# MirrorsDualAttenuverter.net
KiCad netlist of a schematic drawn in EAGLE
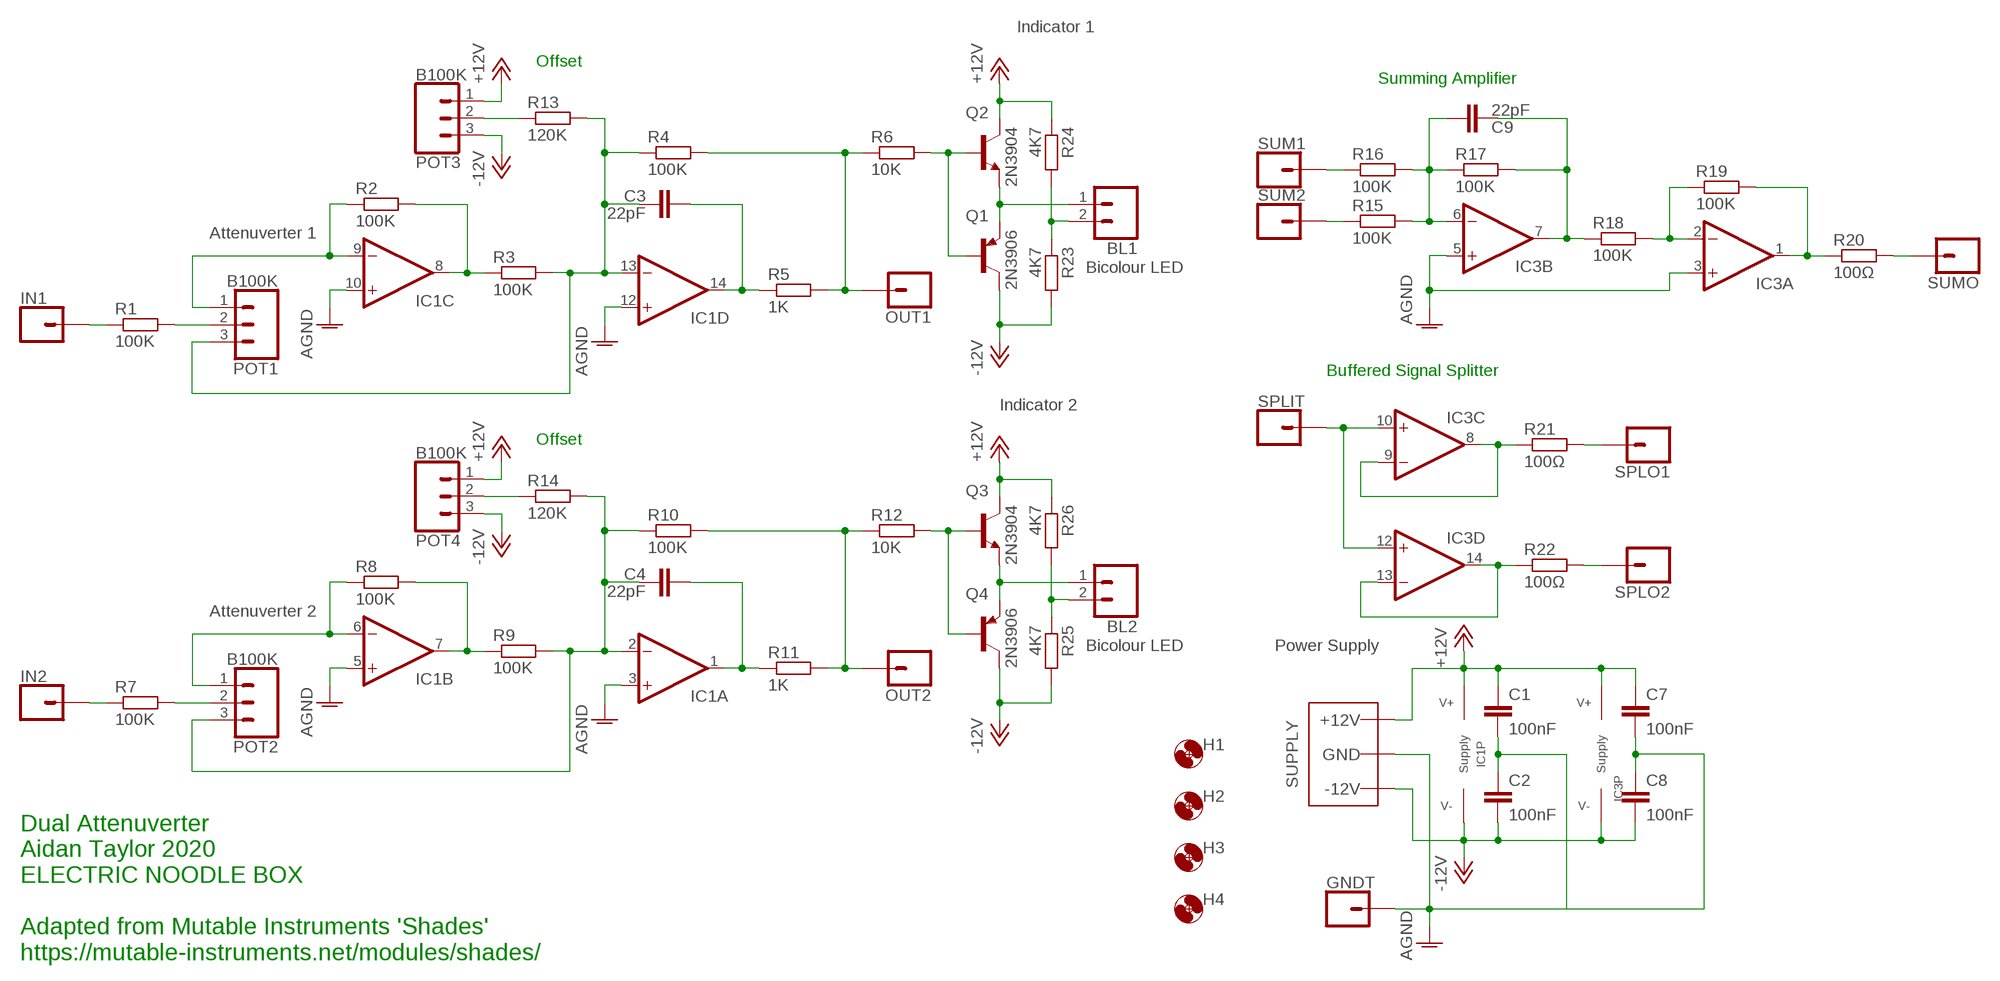
[diagram p0: schematic, sheet 1]

(export (version "E")
  (design (tool "Eeschema 10.0.6"))
  (components
    (comp (ref "BL1")
      (value "2XWIREPAD")
      (footprint "eagle-import:1X02")
      (libsource (lib "eagle-import") (part "2XWIREPAD"))
    )
    (comp (ref "BL2")
      (value "2XWIREPAD")
      (footprint "eagle-import:1X02")
      (libsource (lib "eagle-import") (part "2XWIREPAD"))
    )
    (comp (ref "C1")
      (value "100nF")
      (footprint "eagle-import:C050-025X075")
      (libsource (lib "eagle-import") (part "C-EU050-025X075"))
    )
    (comp (ref "C2")
      (value "100nF")
      (footprint "eagle-import:C050-025X075")
      (libsource (lib "eagle-import") (part "C-EU050-025X075"))
    )
    (comp (ref "C3")
      (value "22pF")
      (footprint "eagle-import:C050-025X075")
      (libsource (lib "eagle-import") (part "C-EU050-025X075"))
    )
    (comp (ref "C4")
      (value "22pF")
      (footprint "eagle-import:C050-025X075")
      (libsource (lib "eagle-import") (part "C-EU050-025X075"))
    )
    (comp (ref "C7")
      (value "100nF")
      (footprint "eagle-import:C050-025X075")
      (libsource (lib "eagle-import") (part "C-EU050-025X075"))
    )
    (comp (ref "C8")
      (value "100nF")
      (footprint "eagle-import:C050-025X075")
      (libsource (lib "eagle-import") (part "C-EU050-025X075"))
    )
    (comp (ref "C9")
      (value "22pF")
      (footprint "eagle-import:C050-025X075")
      (libsource (lib "eagle-import") (part "C-EU050-025X075"))
    )
    (comp (ref "GNDT")
      (value "1XWIREPAD")
      (footprint "eagle-import:1X01")
      (libsource (lib "eagle-import") (part "1XWIREPAD"))
    )
    (comp (ref "H1")
      (value "MOUNT-HOLE3.2")
      (footprint "eagle-import:3,2")
      (libsource (lib "eagle-import") (part "MOUNT-HOLE3.2"))
    )
    (comp (ref "H2")
      (value "MOUNT-HOLE3.2")
      (footprint "eagle-import:3,2")
      (libsource (lib "eagle-import") (part "MOUNT-HOLE3.2"))
    )
    (comp (ref "H3")
      (value "MOUNT-HOLE3.2")
      (footprint "eagle-import:3,2")
      (libsource (lib "eagle-import") (part "MOUNT-HOLE3.2"))
    )
    (comp (ref "H4")
      (value "MOUNT-HOLE3.2")
      (footprint "eagle-import:3,2")
      (libsource (lib "eagle-import") (part "MOUNT-HOLE3.2"))
    )
    (comp (ref "IC1")
      (value "TL0X4DIL")
      (footprint "eagle-import:DIL14")
      (libsource (lib "eagle-import") (part "TL0X4DIL"))
    )
    (comp (ref "IC3")
      (value "TL0X4DIL")
      (footprint "eagle-import:DIL14")
      (libsource (lib "eagle-import") (part "TL0X4DIL"))
    )
    (comp (ref "IN1")
      (value "1XWIREPAD")
      (footprint "eagle-import:1X01")
      (libsource (lib "eagle-import") (part "1XWIREPAD"))
    )
    (comp (ref "IN2")
      (value "1XWIREPAD")
      (footprint "eagle-import:1X01")
      (libsource (lib "eagle-import") (part "1XWIREPAD"))
    )
    (comp (ref "OUT1")
      (value "1XWIREPAD")
      (footprint "eagle-import:1X01")
      (libsource (lib "eagle-import") (part "1XWIREPAD"))
    )
    (comp (ref "OUT2")
      (value "1XWIREPAD")
      (footprint "eagle-import:1X01")
      (libsource (lib "eagle-import") (part "1XWIREPAD"))
    )
    (comp (ref "POT1")
      (value "B100K")
      (footprint "eagle-import:1X03")
      (libsource (lib "eagle-import") (part "3XWIREPAD"))
    )
    (comp (ref "POT2")
      (value "B100K")
      (footprint "eagle-import:1X03")
      (libsource (lib "eagle-import") (part "3XWIREPAD"))
    )
    (comp (ref "POT3")
      (value "B100K")
      (footprint "eagle-import:1X03")
      (libsource (lib "eagle-import") (part "3XWIREPAD"))
    )
    (comp (ref "POT4")
      (value "B100K")
      (footprint "eagle-import:1X03")
      (libsource (lib "eagle-import") (part "3XWIREPAD"))
    )
    (comp (ref "Q1")
      (value "2N3906")
      (footprint "eagle-import:TO92")
      (libsource (lib "eagle-import") (part "2N3906"))
    )
    (comp (ref "Q2")
      (value "2N3904")
      (footprint "eagle-import:TO92")
      (libsource (lib "eagle-import") (part "2N3904"))
    )
    (comp (ref "Q3")
      (value "2N3904")
      (footprint "eagle-import:TO92")
      (libsource (lib "eagle-import") (part "2N3904"))
    )
    (comp (ref "Q4")
      (value "2N3906")
      (footprint "eagle-import:TO92")
      (libsource (lib "eagle-import") (part "2N3906"))
    )
    (comp (ref "R1")
      (value "100K")
      (footprint "eagle-import:0207_10")
      (libsource (lib "eagle-import") (part "R-EU_0207/10"))
    )
    (comp (ref "R2")
      (value "100K")
      (footprint "eagle-import:0207_10")
      (libsource (lib "eagle-import") (part "R-EU_0207/10"))
    )
    (comp (ref "R3")
      (value "100K")
      (footprint "eagle-import:0207_10")
      (libsource (lib "eagle-import") (part "R-EU_0207/10"))
    )
    (comp (ref "R4")
      (value "100K")
      (footprint "eagle-import:0207_10")
      (libsource (lib "eagle-import") (part "R-EU_0207/10"))
    )
    (comp (ref "R5")
      (value "1K")
      (footprint "eagle-import:0207_10")
      (libsource (lib "eagle-import") (part "R-EU_0207/10"))
    )
    (comp (ref "R6")
      (value "10K")
      (footprint "eagle-import:0207_10")
      (libsource (lib "eagle-import") (part "R-EU_0207/10"))
    )
    (comp (ref "R7")
      (value "100K")
      (footprint "eagle-import:0207_10")
      (libsource (lib "eagle-import") (part "R-EU_0207/10"))
    )
    (comp (ref "R8")
      (value "100K")
      (footprint "eagle-import:0207_10")
      (libsource (lib "eagle-import") (part "R-EU_0207/10"))
    )
    (comp (ref "R9")
      (value "100K")
      (footprint "eagle-import:0207_10")
      (libsource (lib "eagle-import") (part "R-EU_0207/10"))
    )
    (comp (ref "R10")
      (value "100K")
      (footprint "eagle-import:0207_10")
      (libsource (lib "eagle-import") (part "R-EU_0207/10"))
    )
    (comp (ref "R11")
      (value "1K")
      (footprint "eagle-import:0207_10")
      (libsource (lib "eagle-import") (part "R-EU_0207/10"))
    )
    (comp (ref "R12")
      (value "10K")
      (footprint "eagle-import:0207_10")
      (libsource (lib "eagle-import") (part "R-EU_0207/10"))
    )
    (comp (ref "R13")
      (value "120K")
      (footprint "eagle-import:0207_10")
      (libsource (lib "eagle-import") (part "R-EU_0207/10"))
    )
    (comp (ref "R14")
      (value "120K")
      (footprint "eagle-import:0207_10")
      (libsource (lib "eagle-import") (part "R-EU_0207/10"))
    )
    (comp (ref "R15")
      (value "100K")
      (footprint "eagle-import:0207_10")
      (libsource (lib "eagle-import") (part "R-EU_0207/10"))
    )
    (comp (ref "R16")
      (value "100K")
      (footprint "eagle-import:0207_10")
      (libsource (lib "eagle-import") (part "R-EU_0207/10"))
    )
    (comp (ref "R17")
      (value "100K")
      (footprint "eagle-import:0207_10")
      (libsource (lib "eagle-import") (part "R-EU_0207/10"))
    )
    (comp (ref "R18")
      (value "100K")
      (footprint "eagle-import:0207_10")
      (libsource (lib "eagle-import") (part "R-EU_0207/10"))
    )
    (comp (ref "R19")
      (value "100K")
      (footprint "eagle-import:0207_10")
      (libsource (lib "eagle-import") (part "R-EU_0207/10"))
    )
    (comp (ref "R20")
      (value "100Ω")
      (footprint "eagle-import:0207_10")
      (libsource (lib "eagle-import") (part "R-EU_0207/10"))
    )
    (comp (ref "R21")
      (value "100Ω")
      (footprint "eagle-import:0207_10")
      (libsource (lib "eagle-import") (part "R-EU_0207/10"))
    )
    (comp (ref "R22")
      (value "100Ω")
      (footprint "eagle-import:0207_10")
      (libsource (lib "eagle-import") (part "R-EU_0207/10"))
    )
    (comp (ref "R23")
      (value "4K7")
      (footprint "eagle-import:0207_10")
      (libsource (lib "eagle-import") (part "R-EU_0207/10"))
    )
    (comp (ref "R24")
      (value "4K7")
      (footprint "eagle-import:0207_10")
      (libsource (lib "eagle-import") (part "R-EU_0207/10"))
    )
    (comp (ref "R25")
      (value "4K7")
      (footprint "eagle-import:0207_10")
      (libsource (lib "eagle-import") (part "R-EU_0207/10"))
    )
    (comp (ref "R26")
      (value "4K7")
      (footprint "eagle-import:0207_10")
      (libsource (lib "eagle-import") (part "R-EU_0207/10"))
    )
    (comp (ref "SPLIT")
      (value "1XWIREPAD")
      (footprint "eagle-import:1X01")
      (libsource (lib "eagle-import") (part "1XWIREPAD"))
    )
    (comp (ref "SPLO1")
      (value "1XWIREPAD")
      (footprint "eagle-import:1X01")
      (libsource (lib "eagle-import") (part "1XWIREPAD"))
    )
    (comp (ref "SPLO2")
      (value "1XWIREPAD")
      (footprint "eagle-import:1X01")
      (libsource (lib "eagle-import") (part "1XWIREPAD"))
    )
    (comp (ref "SUM1")
      (value "1XWIREPAD")
      (footprint "eagle-import:1X01")
      (libsource (lib "eagle-import") (part "1XWIREPAD"))
    )
    (comp (ref "SUM2")
      (value "1XWIREPAD")
      (footprint "eagle-import:1X01")
      (libsource (lib "eagle-import") (part "1XWIREPAD"))
    )
    (comp (ref "SUMO")
      (value "1XWIREPAD")
      (footprint "eagle-import:1X01")
      (libsource (lib "eagle-import") (part "1XWIREPAD"))
    )
    (comp (ref "WP1")
      (value "COMBO_SUPPLY_HEADER")
      (footprint "eagle-import:COMBINED_POWER")
      (libsource (lib "eagle-import") (part "COMBO_SUPPLY_HEADER"))
    )
  )
  (nets
    (net (code "1") (name "+12V") (class "Default")
      (node (ref "C1") (pin "1") (pinfunction "1_1") (pintype "passive"))
      (node (ref "C7") (pin "1") (pinfunction "1_1") (pintype "passive"))
      (node (ref "IC1") (pin "4") (pinfunction "V+_4") (pintype "bidirectional"))
      (node (ref "IC3") (pin "4") (pinfunction "V+_4") (pintype "bidirectional"))
      (node (ref "POT3") (pin "1") (pinfunction "1_1") (pintype "passive"))
      (node (ref "POT4") (pin "1") (pinfunction "1_1") (pintype "passive"))
      (node (ref "Q2") (pin "1") (pinfunction "C_1") (pintype "passive"))
      (node (ref "Q3") (pin "1") (pinfunction "C_1") (pintype "passive"))
      (node (ref "R24") (pin "1") (pinfunction "1_1") (pintype "passive"))
      (node (ref "R26") (pin "1") (pinfunction "1_1") (pintype "passive"))
      (node (ref "WP1") (pin "V+1") (pinfunction "V++_V+1") (pintype "power_in"))
      (node (ref "WP1") (pin "V+2") (pinfunction "V++_V+2") (pintype "power_in"))
      (node (ref "WP1") (pin "V+3") (pinfunction "V++_V+3") (pintype "power_in"))
    )
    (net (code "2") (name "-12V") (class "Default")
      (node (ref "C2") (pin "2") (pinfunction "2_2") (pintype "passive"))
      (node (ref "C8") (pin "2") (pinfunction "2_2") (pintype "passive"))
      (node (ref "IC1") (pin "11") (pinfunction "V-_11") (pintype "bidirectional"))
      (node (ref "IC3") (pin "11") (pinfunction "V-_11") (pintype "bidirectional"))
      (node (ref "POT3") (pin "3") (pinfunction "3_3") (pintype "passive"))
      (node (ref "POT4") (pin "3") (pinfunction "3_3") (pintype "passive"))
      (node (ref "Q1") (pin "1") (pinfunction "C_1") (pintype "passive"))
      (node (ref "Q4") (pin "1") (pinfunction "C_1") (pintype "passive"))
      (node (ref "R23") (pin "2") (pinfunction "2_2") (pintype "passive"))
      (node (ref "R25") (pin "2") (pinfunction "2_2") (pintype "passive"))
      (node (ref "WP1") (pin "V-1") (pinfunction "V--_V-1") (pintype "power_in"))
      (node (ref "WP1") (pin "V-2") (pinfunction "V--_V-2") (pintype "power_in"))
      (node (ref "WP1") (pin "V-3") (pinfunction "V--_V-3") (pintype "power_in"))
    )
    (net (code "3") (name "AGND") (class "Default")
      (node (ref "C1") (pin "2") (pinfunction "2_2") (pintype "passive"))
      (node (ref "C2") (pin "1") (pinfunction "1_1") (pintype "passive"))
      (node (ref "C7") (pin "2") (pinfunction "2_2") (pintype "passive"))
      (node (ref "C8") (pin "1") (pinfunction "1_1") (pintype "passive"))
      (node (ref "GNDT") (pin "1") (pinfunction "1_1") (pintype "passive"))
      (node (ref "IC1") (pin "10") (pinfunction "+IN_10") (pintype "input"))
      (node (ref "IC1") (pin "12") (pinfunction "+IN_12") (pintype "input"))
      (node (ref "IC1") (pin "3") (pinfunction "+IN_3") (pintype "input"))
      (node (ref "IC1") (pin "5") (pinfunction "+IN_5") (pintype "input"))
      (node (ref "IC3") (pin "3") (pinfunction "+IN_3") (pintype "input"))
      (node (ref "IC3") (pin "5") (pinfunction "+IN_5") (pintype "input"))
      (node (ref "WP1") (pin "GND1") (pinfunction "AGND_GND1") (pintype "power_in"))
      (node (ref "WP1") (pin "GND2") (pinfunction "AGND_GND2") (pintype "power_in"))
      (node (ref "WP1") (pin "GND3") (pinfunction "AGND_GND3") (pintype "power_in"))
      (node (ref "WP1") (pin "GND4") (pinfunction "AGND_GND4") (pintype "power_in"))
      (node (ref "WP1") (pin "GND5") (pinfunction "AGND_GND5") (pintype "power_in"))
      (node (ref "WP1") (pin "GND6") (pinfunction "AGND_GND6") (pintype "power_in"))
      (node (ref "WP1") (pin "GND7") (pinfunction "AGND_GND7") (pintype "power_in"))
      (node (ref "WP1") (pin "GND8") (pinfunction "AGND_GND8") (pintype "power_in"))
    )
    (net (code "4") (name "Net-(BL1-Pad2)") (class "Default")
      (node (ref "BL1") (pin "2") (pinfunction "2_2") (pintype "passive"))
      (node (ref "R23") (pin "1") (pinfunction "1_1") (pintype "passive"))
      (node (ref "R24") (pin "2") (pinfunction "2_2") (pintype "passive"))
    )
    (net (code "5") (name "Net-(BL2-Pad2)") (class "Default")
      (node (ref "BL2") (pin "2") (pinfunction "2_2") (pintype "passive"))
      (node (ref "R25") (pin "1") (pinfunction "1_1") (pintype "passive"))
      (node (ref "R26") (pin "2") (pinfunction "2_2") (pintype "passive"))
    )
    (net (code "6") (name "Net-(IC1A--IN)") (class "Default")
      (node (ref "C4") (pin "1") (pinfunction "1_1") (pintype "passive"))
      (node (ref "IC1") (pin "2") (pinfunction "-IN_2") (pintype "input"))
      (node (ref "POT2") (pin "3") (pinfunction "3_3") (pintype "passive"))
      (node (ref "R10") (pin "1") (pinfunction "1_1") (pintype "passive"))
      (node (ref "R14") (pin "2") (pinfunction "2_2") (pintype "passive"))
      (node (ref "R9") (pin "2") (pinfunction "2_2") (pintype "passive"))
    )
    (net (code "7") (name "Net-(IC1A-OUT)") (class "Default")
      (node (ref "C4") (pin "2") (pinfunction "2_2") (pintype "passive"))
      (node (ref "IC1") (pin "1") (pinfunction "OUT_1") (pintype "output"))
      (node (ref "R11") (pin "1") (pinfunction "1_1") (pintype "passive"))
    )
    (net (code "8") (name "Net-(IC1B--IN)") (class "Default")
      (node (ref "IC1") (pin "6") (pinfunction "-IN_6") (pintype "input"))
      (node (ref "POT2") (pin "1") (pinfunction "1_1") (pintype "passive"))
      (node (ref "R8") (pin "1") (pinfunction "1_1") (pintype "passive"))
    )
    (net (code "9") (name "Net-(IC1B-OUT)") (class "Default")
      (node (ref "IC1") (pin "7") (pinfunction "OUT_7") (pintype "output"))
      (node (ref "R8") (pin "2") (pinfunction "2_2") (pintype "passive"))
      (node (ref "R9") (pin "1") (pinfunction "1_1") (pintype "passive"))
    )
    (net (code "10") (name "Net-(IC1C--IN)") (class "Default")
      (node (ref "IC1") (pin "9") (pinfunction "-IN_9") (pintype "input"))
      (node (ref "POT1") (pin "1") (pinfunction "1_1") (pintype "passive"))
      (node (ref "R2") (pin "1") (pinfunction "1_1") (pintype "passive"))
    )
    (net (code "11") (name "Net-(IC1C-OUT)") (class "Default")
      (node (ref "IC1") (pin "8") (pinfunction "OUT_8") (pintype "output"))
      (node (ref "R2") (pin "2") (pinfunction "2_2") (pintype "passive"))
      (node (ref "R3") (pin "1") (pinfunction "1_1") (pintype "passive"))
    )
    (net (code "12") (name "Net-(IC1D--IN)") (class "Default")
      (node (ref "C3") (pin "1") (pinfunction "1_1") (pintype "passive"))
      (node (ref "IC1") (pin "13") (pinfunction "-IN_13") (pintype "input"))
      (node (ref "POT1") (pin "3") (pinfunction "3_3") (pintype "passive"))
      (node (ref "R13") (pin "2") (pinfunction "2_2") (pintype "passive"))
      (node (ref "R3") (pin "2") (pinfunction "2_2") (pintype "passive"))
      (node (ref "R4") (pin "1") (pinfunction "1_1") (pintype "passive"))
    )
    (net (code "13") (name "Net-(IC1D-OUT)") (class "Default")
      (node (ref "C3") (pin "2") (pinfunction "2_2") (pintype "passive"))
      (node (ref "IC1") (pin "14") (pinfunction "OUT_14") (pintype "output"))
      (node (ref "R5") (pin "1") (pinfunction "1_1") (pintype "passive"))
    )
    (net (code "14") (name "Net-(IC3A--IN)") (class "Default")
      (node (ref "IC3") (pin "2") (pinfunction "-IN_2") (pintype "input"))
      (node (ref "R18") (pin "2") (pinfunction "2_2") (pintype "passive"))
      (node (ref "R19") (pin "1") (pinfunction "1_1") (pintype "passive"))
    )
    (net (code "15") (name "Net-(IC3A-OUT)") (class "Default")
      (node (ref "IC3") (pin "1") (pinfunction "OUT_1") (pintype "output"))
      (node (ref "R19") (pin "2") (pinfunction "2_2") (pintype "passive"))
      (node (ref "R20") (pin "1") (pinfunction "1_1") (pintype "passive"))
    )
    (net (code "16") (name "Net-(IC3B--IN)") (class "Default")
      (node (ref "C9") (pin "2") (pinfunction "2_2") (pintype "passive"))
      (node (ref "IC3") (pin "6") (pinfunction "-IN_6") (pintype "input"))
      (node (ref "R15") (pin "2") (pinfunction "2_2") (pintype "passive"))
      (node (ref "R16") (pin "2") (pinfunction "2_2") (pintype "passive"))
      (node (ref "R17") (pin "1") (pinfunction "1_1") (pintype "passive"))
    )
    (net (code "17") (name "Net-(IC3B-OUT)") (class "Default")
      (node (ref "C9") (pin "1") (pinfunction "1_1") (pintype "passive"))
      (node (ref "IC3") (pin "7") (pinfunction "OUT_7") (pintype "output"))
      (node (ref "R17") (pin "2") (pinfunction "2_2") (pintype "passive"))
      (node (ref "R18") (pin "1") (pinfunction "1_1") (pintype "passive"))
    )
    (net (code "18") (name "Net-(IC3C-+IN)") (class "Default")
      (node (ref "IC3") (pin "10") (pinfunction "+IN_10") (pintype "input"))
      (node (ref "IC3") (pin "12") (pinfunction "+IN_12") (pintype "input"))
      (node (ref "SPLIT") (pin "1") (pinfunction "1_1") (pintype "passive"))
    )
    (net (code "19") (name "Net-(IC3C--IN)") (class "Default")
      (node (ref "IC3") (pin "8") (pinfunction "OUT_8") (pintype "output"))
      (node (ref "IC3") (pin "9") (pinfunction "-IN_9") (pintype "input"))
      (node (ref "R21") (pin "1") (pinfunction "1_1") (pintype "passive"))
    )
    (net (code "20") (name "Net-(IC3D--IN)") (class "Default")
      (node (ref "IC3") (pin "13") (pinfunction "-IN_13") (pintype "input"))
      (node (ref "IC3") (pin "14") (pinfunction "OUT_14") (pintype "output"))
      (node (ref "R22") (pin "1") (pinfunction "1_1") (pintype "passive"))
    )
    (net (code "21") (name "Net-(IN1-Pad1)") (class "Default")
      (node (ref "IN1") (pin "1") (pinfunction "1_1") (pintype "passive"))
      (node (ref "R1") (pin "1") (pinfunction "1_1") (pintype "passive"))
    )
    (net (code "22") (name "Net-(IN2-Pad1)") (class "Default")
      (node (ref "IN2") (pin "1") (pinfunction "1_1") (pintype "passive"))
      (node (ref "R7") (pin "1") (pinfunction "1_1") (pintype "passive"))
    )
    (net (code "23") (name "Net-(OUT1-Pad1)") (class "Default")
      (node (ref "OUT1") (pin "1") (pinfunction "1_1") (pintype "passive"))
      (node (ref "R4") (pin "2") (pinfunction "2_2") (pintype "passive"))
      (node (ref "R5") (pin "2") (pinfunction "2_2") (pintype "passive"))
      (node (ref "R6") (pin "1") (pinfunction "1_1") (pintype "passive"))
    )
    (net (code "24") (name "Net-(OUT2-Pad1)") (class "Default")
      (node (ref "OUT2") (pin "1") (pinfunction "1_1") (pintype "passive"))
      (node (ref "R10") (pin "2") (pinfunction "2_2") (pintype "passive"))
      (node (ref "R11") (pin "2") (pinfunction "2_2") (pintype "passive"))
      (node (ref "R12") (pin "1") (pinfunction "1_1") (pintype "passive"))
    )
    (net (code "25") (name "Net-(POT1-Pad2)") (class "Default")
      (node (ref "POT1") (pin "2") (pinfunction "2_2") (pintype "passive"))
      (node (ref "R1") (pin "2") (pinfunction "2_2") (pintype "passive"))
    )
    (net (code "26") (name "Net-(POT2-Pad2)") (class "Default")
      (node (ref "POT2") (pin "2") (pinfunction "2_2") (pintype "passive"))
      (node (ref "R7") (pin "2") (pinfunction "2_2") (pintype "passive"))
    )
    (net (code "27") (name "Net-(POT3-Pad2)") (class "Default")
      (node (ref "POT3") (pin "2") (pinfunction "2_2") (pintype "passive"))
      (node (ref "R13") (pin "1") (pinfunction "1_1") (pintype "passive"))
    )
    (net (code "28") (name "Net-(POT4-Pad2)") (class "Default")
      (node (ref "POT4") (pin "2") (pinfunction "2_2") (pintype "passive"))
      (node (ref "R14") (pin "1") (pinfunction "1_1") (pintype "passive"))
    )
    (net (code "29") (name "Net-(Q1-B)") (class "Default")
      (node (ref "Q1") (pin "2") (pinfunction "B_2") (pintype "passive"))
      (node (ref "Q2") (pin "2") (pinfunction "B_2") (pintype "passive"))
      (node (ref "R6") (pin "2") (pinfunction "2_2") (pintype "passive"))
    )
    (net (code "30") (name "Net-(Q1-E)") (class "Default")
      (node (ref "BL1") (pin "1") (pinfunction "1_1") (pintype "passive"))
      (node (ref "Q1") (pin "3") (pinfunction "E_3") (pintype "passive"))
      (node (ref "Q2") (pin "3") (pinfunction "E_3") (pintype "passive"))
    )
    (net (code "31") (name "Net-(Q3-B)") (class "Default")
      (node (ref "Q3") (pin "2") (pinfunction "B_2") (pintype "passive"))
      (node (ref "Q4") (pin "2") (pinfunction "B_2") (pintype "passive"))
      (node (ref "R12") (pin "2") (pinfunction "2_2") (pintype "passive"))
    )
    (net (code "32") (name "Net-(Q3-E)") (class "Default")
      (node (ref "BL2") (pin "1") (pinfunction "1_1") (pintype "passive"))
      (node (ref "Q3") (pin "3") (pinfunction "E_3") (pintype "passive"))
      (node (ref "Q4") (pin "3") (pinfunction "E_3") (pintype "passive"))
    )
    (net (code "33") (name "Net-(R15-Pad1)") (class "Default")
      (node (ref "R15") (pin "1") (pinfunction "1_1") (pintype "passive"))
      (node (ref "SUM2") (pin "1") (pinfunction "1_1") (pintype "passive"))
    )
    (net (code "34") (name "Net-(R16-Pad1)") (class "Default")
      (node (ref "R16") (pin "1") (pinfunction "1_1") (pintype "passive"))
      (node (ref "SUM1") (pin "1") (pinfunction "1_1") (pintype "passive"))
    )
    (net (code "35") (name "Net-(R20-Pad2)") (class "Default")
      (node (ref "R20") (pin "2") (pinfunction "2_2") (pintype "passive"))
      (node (ref "SUMO") (pin "1") (pinfunction "1_1") (pintype "passive"))
    )
    (net (code "36") (name "Net-(R21-Pad2)") (class "Default")
      (node (ref "R21") (pin "2") (pinfunction "2_2") (pintype "passive"))
      (node (ref "SPLO1") (pin "1") (pinfunction "1_1") (pintype "passive"))
    )
    (net (code "37") (name "Net-(R22-Pad2)") (class "Default")
      (node (ref "R22") (pin "2") (pinfunction "2_2") (pintype "passive"))
      (node (ref "SPLO2") (pin "1") (pinfunction "1_1") (pintype "passive"))
    )
  )
)
